# Supply.net
KiCad netlist of a schematic drawn in Altium Designer
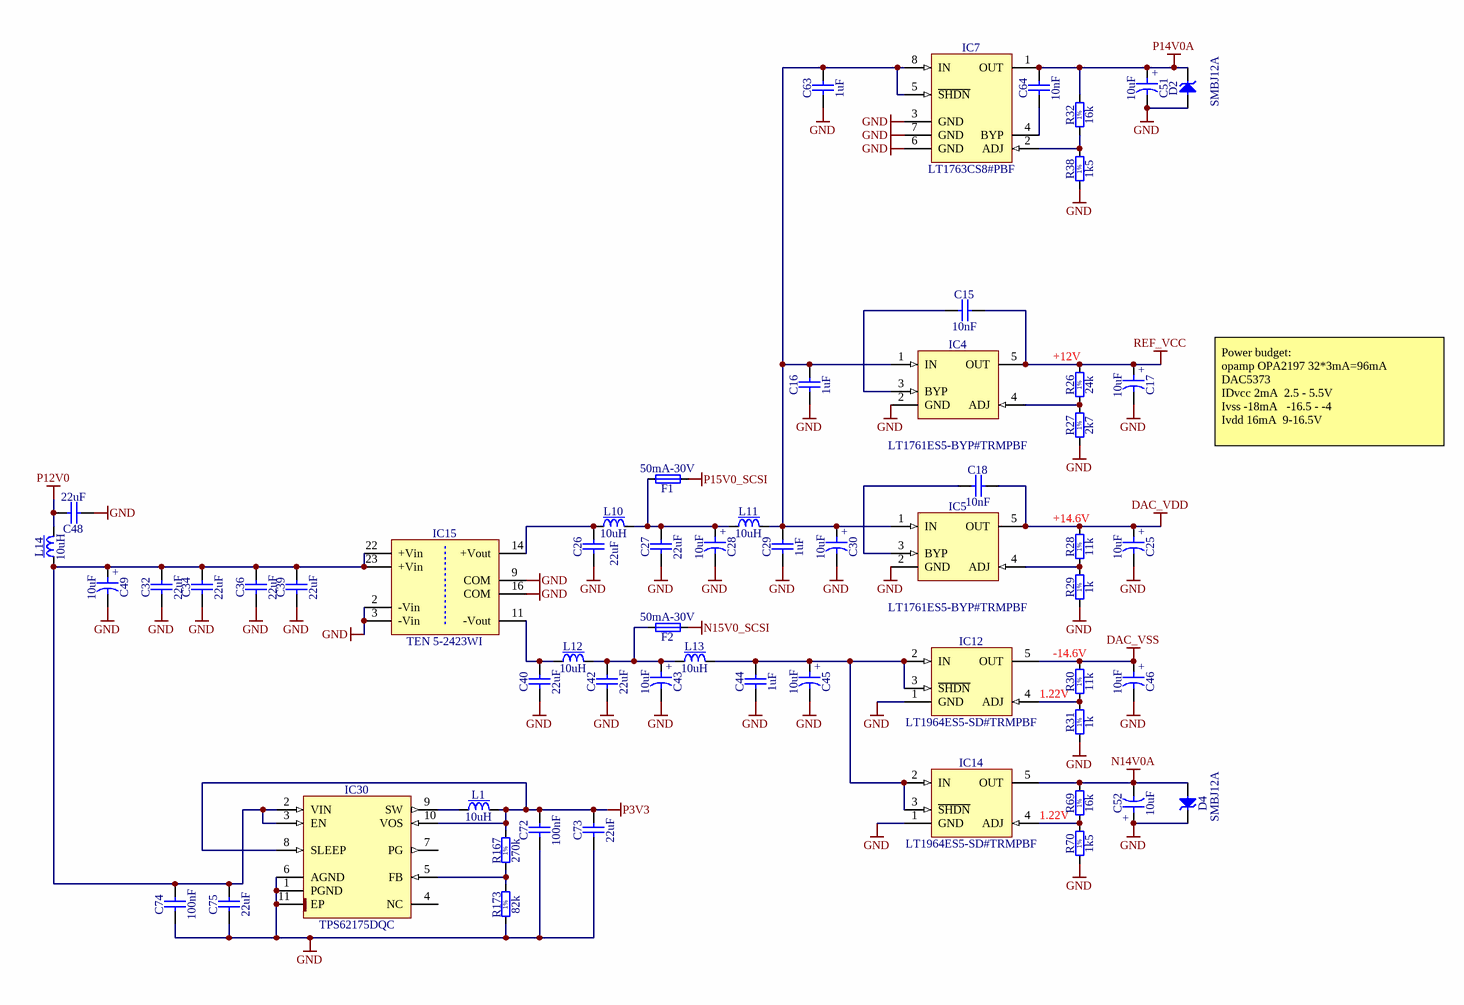
[diagram p0: Supply.SchDoc]

(export (version "E")
  (design (tool "Eeschema 10.0.6"))
  (components
    (comp (ref "C15")
      (value "10nF")
      (footprint "CAPC1608X87N")
      (description "Non-polarised capacitor")
      (fields
        (field (name "PART NUMBER") "CC0603_10NF_50V_10%_X7R")
        (field (name "VOLTAGE") "50V")
        (field (name "AUTHOR") "CERN DEM JLC")
      )
      (libsource (lib "Capacitors") (part "Capacitor - non polarized"))
    )
    (comp (ref "C16")
      (value "1uF")
      (footprint "CAPC1608X87N")
      (description "Non-polarised capacitor")
      (fields
        (field (name "PART NUMBER") "CC0603_1UF_25V_10%_X7R")
        (field (name "VOLTAGE") "25V")
        (field (name "AUTHOR") "CERN DEM JLC")
      )
      (libsource (lib "Capacitors") (part "Capacitor - non polarized"))
    )
    (comp (ref "C17")
      (value "10uF")
      (footprint "CAPMP3216X180N")
      (description "Polarised capacitor")
      (fields
        (field (name "PART NUMBER") "CTE3216-18_10UF_16V_20%_AVX_TCJ")
        (field (name "VOLTAGE") "16V")
        (field (name "AUTHOR") "CERN DEM JLC")
      )
      (libsource (lib "Capacitors") (part "Capacitor - polarized"))
    )
    (comp (ref "C18")
      (value "10nF")
      (footprint "CAPC1608X87N")
      (description "Non-polarised capacitor")
      (fields
        (field (name "PART NUMBER") "CC0603_10NF_50V_10%_X7R")
        (field (name "VOLTAGE") "50V")
        (field (name "AUTHOR") "CERN DEM JLC")
      )
      (libsource (lib "Capacitors") (part "Capacitor - non polarized"))
    )
    (comp (ref "C25")
      (value "10uF")
      (footprint "CAPMP3216X180N")
      (description "Polarised capacitor")
      (fields
        (field (name "PART NUMBER") "CTE3216-18_10UF_16V_20%_AVX_TCJ")
        (field (name "VOLTAGE") "16V")
        (field (name "AUTHOR") "CERN DEM JLC")
      )
      (libsource (lib "Capacitors") (part "Capacitor - polarized"))
    )
    (comp (ref "C26")
      (value "22uF")
      (footprint "CAPC2012X135N")
      (description "Non-polarised capacitor")
      (fields
        (field (name "PART NUMBER") "CC0805_22UF_16V_10%_X5R")
        (field (name "VOLTAGE") "16V")
        (field (name "AUTHOR") "CERN DEM JLC")
      )
      (libsource (lib "Capacitors") (part "Capacitor - non polarized"))
    )
    (comp (ref "C27")
      (value "22uF")
      (footprint "CAPC2012X135N")
      (description "Non-polarised capacitor")
      (fields
        (field (name "PART NUMBER") "CC0805_22UF_16V_10%_X5R")
        (field (name "VOLTAGE") "16V")
        (field (name "AUTHOR") "CERN DEM JLC")
      )
      (libsource (lib "Capacitors") (part "Capacitor - non polarized"))
    )
    (comp (ref "C28")
      (value "10uF")
      (footprint "CAPMP3216X180N")
      (description "Polarised capacitor")
      (fields
        (field (name "PART NUMBER") "CTE3216-18_10UF_16V_20%_AVX_TCJ")
        (field (name "VOLTAGE") "16V")
        (field (name "AUTHOR") "CERN DEM JLC")
      )
      (libsource (lib "Capacitors") (part "Capacitor - polarized"))
    )
    (comp (ref "C29")
      (value "1uF")
      (footprint "CAPC1608X87N")
      (description "Non-polarised capacitor")
      (fields
        (field (name "PART NUMBER") "CC0603_1UF_25V_10%_X7R")
        (field (name "VOLTAGE") "25V")
        (field (name "AUTHOR") "CERN DEM JLC")
      )
      (libsource (lib "Capacitors") (part "Capacitor - non polarized"))
    )
    (comp (ref "C30")
      (value "10uF")
      (footprint "CAPMP3216X180N")
      (description "Polarised capacitor")
      (fields
        (field (name "PART NUMBER") "CTE3216-18_10UF_16V_20%_AVX_TCJ")
        (field (name "VOLTAGE") "16V")
        (field (name "AUTHOR") "CERN DEM JLC")
      )
      (libsource (lib "Capacitors") (part "Capacitor - polarized"))
    )
    (comp (ref "C32")
      (value "22uF")
      (footprint "CAPC2012X135N")
      (description "Non-polarised capacitor")
      (fields
        (field (name "PART NUMBER") "CC0805_22UF_16V_10%_X5R")
        (field (name "VOLTAGE") "16V")
        (field (name "AUTHOR") "CERN DEM JLC")
      )
      (libsource (lib "Capacitors") (part "Capacitor - non polarized"))
    )
    (comp (ref "C34")
      (value "22uF")
      (footprint "CAPC2012X135N")
      (description "Non-polarised capacitor")
      (fields
        (field (name "PART NUMBER") "CC0805_22UF_16V_10%_X5R")
        (field (name "VOLTAGE") "16V")
        (field (name "AUTHOR") "CERN DEM JLC")
      )
      (libsource (lib "Capacitors") (part "Capacitor - non polarized"))
    )
    (comp (ref "C36")
      (value "22uF")
      (footprint "CAPC2012X135N")
      (description "Non-polarised capacitor")
      (fields
        (field (name "PART NUMBER") "CC0805_22UF_16V_10%_X5R")
        (field (name "VOLTAGE") "16V")
        (field (name "AUTHOR") "CERN DEM JLC")
      )
      (libsource (lib "Capacitors") (part "Capacitor - non polarized"))
    )
    (comp (ref "C39")
      (value "22uF")
      (footprint "CAPC2012X135N")
      (description "Non-polarised capacitor")
      (fields
        (field (name "PART NUMBER") "CC0805_22UF_16V_10%_X5R")
        (field (name "VOLTAGE") "16V")
        (field (name "AUTHOR") "CERN DEM JLC")
      )
      (libsource (lib "Capacitors") (part "Capacitor - non polarized"))
    )
    (comp (ref "C40")
      (value "22uF")
      (footprint "CAPC2012X135N")
      (description "Non-polarised capacitor")
      (fields
        (field (name "PART NUMBER") "CC0805_22UF_16V_10%_X5R")
        (field (name "VOLTAGE") "16V")
        (field (name "AUTHOR") "CERN DEM JLC")
      )
      (libsource (lib "Capacitors") (part "Capacitor - non polarized"))
    )
    (comp (ref "C42")
      (value "22uF")
      (footprint "CAPC2012X135N")
      (description "Non-polarised capacitor")
      (fields
        (field (name "PART NUMBER") "CC0805_22UF_16V_10%_X5R")
        (field (name "VOLTAGE") "16V")
        (field (name "AUTHOR") "CERN DEM JLC")
      )
      (libsource (lib "Capacitors") (part "Capacitor - non polarized"))
    )
    (comp (ref "C43")
      (value "10uF")
      (footprint "CAPMP3216X180N")
      (description "Polarised capacitor")
      (fields
        (field (name "PART NUMBER") "CTE3216-18_10UF_16V_20%_AVX_TCJ")
        (field (name "VOLTAGE") "16V")
        (field (name "AUTHOR") "CERN DEM JLC")
      )
      (libsource (lib "Capacitors") (part "Capacitor - polarized"))
    )
    (comp (ref "C44")
      (value "1uF")
      (footprint "CAPC1608X87N")
      (description "Non-polarised capacitor")
      (fields
        (field (name "PART NUMBER") "CC0603_1UF_25V_10%_X7R")
        (field (name "VOLTAGE") "25V")
        (field (name "AUTHOR") "CERN DEM JLC")
      )
      (libsource (lib "Capacitors") (part "Capacitor - non polarized"))
    )
    (comp (ref "C45")
      (value "10uF")
      (footprint "CAPMP3216X180N")
      (description "Polarised capacitor")
      (fields
        (field (name "PART NUMBER") "CTE3216-18_10UF_16V_20%_AVX_TCJ")
        (field (name "VOLTAGE") "16V")
        (field (name "AUTHOR") "CERN DEM JLC")
      )
      (libsource (lib "Capacitors") (part "Capacitor - polarized"))
    )
    (comp (ref "C46")
      (value "10uF")
      (footprint "CAPMP3216X180N")
      (description "Polarised capacitor")
      (fields
        (field (name "PART NUMBER") "CTE3216-18_10UF_16V_20%_AVX_TCJ")
        (field (name "VOLTAGE") "16V")
        (field (name "AUTHOR") "CERN DEM JLC")
      )
      (libsource (lib "Capacitors") (part "Capacitor - polarized"))
    )
    (comp (ref "C48")
      (value "22uF")
      (footprint "CAPC2012X135N")
      (description "Non-polarised capacitor")
      (fields
        (field (name "PART NUMBER") "CC0805_22UF_16V_10%_X5R")
        (field (name "VOLTAGE") "16V")
        (field (name "AUTHOR") "CERN DEM JLC")
      )
      (libsource (lib "Capacitors") (part "Capacitor - non polarized"))
    )
    (comp (ref "C49")
      (value "10uF")
      (footprint "CAPMP3216X180N")
      (description "Polarised capacitor")
      (fields
        (field (name "PART NUMBER") "CTE3216-18_10UF_16V_20%_AVX_TCJ")
        (field (name "VOLTAGE") "16V")
        (field (name "AUTHOR") "CERN DEM JLC")
      )
      (libsource (lib "Capacitors") (part "Capacitor - polarized"))
    )
    (comp (ref "C51")
      (value "10uF")
      (footprint "CAPMP3216X180N")
      (description "Polarised capacitor")
      (fields
        (field (name "PART NUMBER") "CTE3216-18_10UF_16V_20%_AVX_TCJ")
        (field (name "VOLTAGE") "16V")
        (field (name "AUTHOR") "CERN DEM JLC")
      )
      (libsource (lib "Capacitors") (part "Capacitor - polarized"))
    )
    (comp (ref "C52")
      (value "10uF")
      (footprint "CAPMP3216X180N")
      (description "Polarised capacitor")
      (fields
        (field (name "PART NUMBER") "CTE3216-18_10UF_16V_20%_AVX_TCJ")
        (field (name "VOLTAGE") "16V")
        (field (name "AUTHOR") "CERN DEM JLC")
      )
      (libsource (lib "Capacitors") (part "Capacitor - polarized"))
    )
    (comp (ref "C63")
      (value "1uF")
      (footprint "CAPC1608X87N")
      (description "Non-polarised capacitor")
      (fields
        (field (name "PART NUMBER") "CC0603_1UF_25V_10%_X7R")
        (field (name "VOLTAGE") "25V")
        (field (name "AUTHOR") "CERN DEM JLC")
      )
      (libsource (lib "Capacitors") (part "Capacitor - non polarized"))
    )
    (comp (ref "C64")
      (value "10nF")
      (footprint "CAPC1608X87N")
      (description "Non-polarised capacitor")
      (fields
        (field (name "PART NUMBER") "CC0603_10NF_50V_10%_X7R")
        (field (name "VOLTAGE") "50V")
        (field (name "AUTHOR") "CERN DEM JLC")
      )
      (libsource (lib "Capacitors") (part "Capacitor - non polarized"))
    )
    (comp (ref "C72")
      (value "100nF")
      (footprint "CAPC1005X55N")
      (description "Non-polarised capacitor")
      (fields
        (field (name "PART NUMBER") "CC0402_100NF_16V_10%_X5R")
        (field (name "VOLTAGE") "16V")
        (field (name "AUTHOR") "CERN DEM JLC")
      )
      (libsource (lib "Capacitors") (part "Capacitor - non polarized"))
    )
    (comp (ref "C73")
      (value "22uF")
      (footprint "CAPC2012X135N")
      (description "Non-polarised capacitor")
      (fields
        (field (name "PART NUMBER") "CC0805_22UF_16V_10%_X5R")
        (field (name "VOLTAGE") "16V")
        (field (name "AUTHOR") "CERN DEM JLC")
      )
      (libsource (lib "Capacitors") (part "Capacitor - non polarized"))
    )
    (comp (ref "C74")
      (value "100nF")
      (footprint "CAPC1005X55N")
      (description "Non-polarised capacitor")
      (fields
        (field (name "PART NUMBER") "CC0402_100NF_16V_10%_X5R")
        (field (name "VOLTAGE") "16V")
        (field (name "AUTHOR") "CERN DEM JLC")
      )
      (libsource (lib "Capacitors") (part "Capacitor - non polarized"))
    )
    (comp (ref "C75")
      (value "22uF")
      (footprint "CAPC2012X135N")
      (description "Non-polarised capacitor")
      (fields
        (field (name "PART NUMBER") "CC0805_22UF_16V_10%_X5R")
        (field (name "VOLTAGE") "16V")
        (field (name "AUTHOR") "CERN DEM JLC")
      )
      (libsource (lib "Capacitors") (part "Capacitor - non polarized"))
    )
    (comp (ref "D2")
      (value "SMBJ12A")
      (footprint "DIOM5336X265N")
      (description "Zener Diode")
      (fields
        (field (name "VOLTAGE") "12V")
        (field (name "POWER") "600W")
        (field (name "AUTHOR") "CERN DEM JLC")
      )
      (libsource (lib "ICs And Semiconductors") (part "Diode Zener"))
    )
    (comp (ref "D4")
      (value "SMBJ12A")
      (footprint "DIOM5336X265N")
      (description "Zener Diode")
      (fields
        (field (name "VOLTAGE") "12V")
        (field (name "POWER") "600W")
        (field (name "AUTHOR") "CERN DEM JLC")
      )
      (libsource (lib "ICs And Semiconductors") (part "Diode Zener"))
    )
    (comp (ref "F1")
      (value "50mA-30V")
      (footprint "FUSRC3226X85N")
      (description "Fuse")
      (fields
        (field (name "PART NUMBER") "FUSR1210_TYCO-MICROSMD005F")
        (field (name "MANUFACTURER") "TYCO ELECTRONICS")
        (field (name "AUTHOR") "CERN DEM JLC")
      )
      (libsource (lib "Eletro-mechanical") (part "Fuse"))
    )
    (comp (ref "F2")
      (value "50mA-30V")
      (footprint "FUSRC3226X85N")
      (description "Fuse")
      (fields
        (field (name "PART NUMBER") "FUSR1210_TYCO-MICROSMD005F")
        (field (name "MANUFACTURER") "TYCO ELECTRONICS")
        (field (name "AUTHOR") "CERN DEM JLC")
      )
      (libsource (lib "Eletro-mechanical") (part "Fuse"))
    )
    (comp (ref "IC4")
      (value "LT1761ES5-BYP#TRMPBF")
      (footprint "SOT95P280X100-5N")
      (description "100mA, Low Noise, LDO Micropower Adjustable Regulator in SOT-23")
      (fields (field (name "MANUFACTURER") "LINEAR TECHNOLOGY") (field (name "AUTHOR") "CERN DEM MR"))
      (libsource (lib "ICs And Semiconductors") (part "LT1761-BYP"))
    )
    (comp (ref "IC5")
      (value "LT1761ES5-BYP#TRMPBF")
      (footprint "SOT95P280X100-5N")
      (description "100mA, Low Noise, LDO Micropower Adjustable Regulator in SOT-23")
      (fields (field (name "MANUFACTURER") "LINEAR TECHNOLOGY") (field (name "AUTHOR") "CERN DEM MR"))
      (libsource (lib "ICs And Semiconductors") (part "LT1761-BYP"))
    )
    (comp (ref "IC7")
      (value "LT1763CS8#PBF")
      (footprint "SOIC127P600X175-8N")
      (description "1.22V to 20V 500mA, Low Noise, LDO Adjustable Micropower Regulator")
      (fields (field (name "MANUFACTURER") "LINEAR TECHNOLOGY") (field (name "AUTHOR") "CERN DEM JLC"))
      (libsource (lib "ICs And Semiconductors") (part "LT1763xS8"))
    )
    (comp (ref "IC12")
      (value "LT1964ES5-SD#TRMPBF")
      (footprint "SOT95P280X100-5N")
      (description "200mA, Low Noise, Low Dropout Negative Micropower Regulator")
      (fields (field (name "MANUFACTURER") "LINEAR TECHNOLOGY") (field (name "AUTHOR") "CERN DEM JLC"))
      (libsource (lib "ICs And Semiconductors") (part "LT1964-SD"))
    )
    (comp (ref "IC14")
      (value "LT1964ES5-SD#TRMPBF")
      (footprint "SOT95P280X100-5N")
      (description "200mA, Low Noise, Low Dropout Negative Micropower Regulator")
      (fields (field (name "MANUFACTURER") "LINEAR TECHNOLOGY") (field (name "AUTHOR") "CERN DEM JLC"))
      (libsource (lib "ICs And Semiconductors") (part "LT1964-SD"))
    )
    (comp (ref "IC15")
      (value "TEN 5-2423WI")
      (footprint "DCDC_TRACO_TEN5WI")
      (description "TRACO, TEN5 Serie, Dual Outputs DCDC Converter")
      (fields (field (name "MANUFACTURER") "TRACO POWER") (field (name "AUTHOR") "CERN DEM JMW"))
      (libsource (lib "ICs And Semiconductors") (part "DCDC_TRACO_TEN5_Dual Outputs"))
    )
    (comp (ref "IC30")
      (value "TPS62175DQC")
      (footprint "SON50P200X300X80-11N-R94X250")
      (description "4.75-28VDC to 1-6VDC, 500mA Step-Down Converter With Sleep Mode")
      (fields (field (name "MANUFACTURER") "TEXAS INSTRUMENTS") (field (name "AUTHOR") "CERN DEM JMW"))
      (libsource (lib "ICs And Semiconductors") (part "TPS62175"))
    )
    (comp (ref "L1")
      (value "10uH")
      (footprint "IND_MURATA-PS_8400")
      (description "Inductor With Core")
      (fields
        (field (name "PART NUMBER") "IND_10UH_10%_MURATA-PS_8400")
        (field (name "POWER") "950mA")
        (field (name "AUTHOR") "CERN DEM JLC")
      )
      (libsource (lib "") (part "Inductor With Magnetic core_1"))
    )
    (comp (ref "L10")
      (value "10uH")
      (footprint "IND_MURATA-PS_8400")
      (description "Inductor With Core")
      (fields
        (field (name "PART NUMBER") "IND_10UH_10%_MURATA-PS_8400")
        (field (name "POWER") "950mA")
        (field (name "AUTHOR") "CERN DEM JLC")
      )
      (libsource (lib "") (part "Inductor With Magnetic core_1"))
    )
    (comp (ref "L11")
      (value "10uH")
      (footprint "IND_MURATA-PS_8400")
      (description "Inductor With Core")
      (fields
        (field (name "PART NUMBER") "IND_10UH_10%_MURATA-PS_8400")
        (field (name "POWER") "950mA")
        (field (name "AUTHOR") "CERN DEM JLC")
      )
      (libsource (lib "") (part "Inductor With Magnetic core_1"))
    )
    (comp (ref "L12")
      (value "10uH")
      (footprint "IND_MURATA-PS_8400")
      (description "Inductor With Core")
      (fields
        (field (name "PART NUMBER") "IND_10UH_10%_MURATA-PS_8400")
        (field (name "POWER") "950mA")
        (field (name "AUTHOR") "CERN DEM JLC")
      )
      (libsource (lib "") (part "Inductor With Magnetic core_1"))
    )
    (comp (ref "L13")
      (value "10uH")
      (footprint "IND_MURATA-PS_8400")
      (description "Inductor With Core")
      (fields
        (field (name "PART NUMBER") "IND_10UH_10%_MURATA-PS_8400")
        (field (name "POWER") "950mA")
        (field (name "AUTHOR") "CERN DEM JLC")
      )
      (libsource (lib "") (part "Inductor With Magnetic core_1"))
    )
    (comp (ref "L14")
      (value "10uH")
      (footprint "IND_MURATA-PS_8400")
      (description "Inductor With Core")
      (fields
        (field (name "PART NUMBER") "IND_10UH_10%_MURATA-PS_8400")
        (field (name "POWER") "950mA")
        (field (name "AUTHOR") "CERN DEM JLC")
      )
      (libsource (lib "Inductors & Transformers") (part "Inductor With Magnetic core"))
    )
    (comp (ref "R26")
      (value "24k")
      (footprint "RESC1608X55N")
      (description "Resistor - 1%")
      (fields
        (field (name "PART NUMBER") "R0603_24K_1%_0.1W_100PPM")
        (field (name "POWER") "0.1W")
        (field (name "AUTHOR") "CERN DEM JLC")
      )
      (libsource (lib "Resistors") (part "Resistor - 1%"))
    )
    (comp (ref "R27")
      (value "2k7")
      (footprint "RESC1608X55N")
      (description "Resistor - 1%")
      (fields
        (field (name "PART NUMBER") "R0603_2K7_1%_0.1W_100PPM")
        (field (name "POWER") "0.1W")
        (field (name "AUTHOR") "CERN DEM JLC")
      )
      (libsource (lib "Resistors") (part "Resistor - 1%"))
    )
    (comp (ref "R28")
      (value "11k")
      (footprint "RESC1608X55N")
      (description "Resistor - 1%")
      (fields
        (field (name "PART NUMBER") "R0603_11K_1%_0.1W_100PPM")
        (field (name "POWER") "0.1W")
        (field (name "AUTHOR") "CERN DEM JLC")
      )
      (libsource (lib "Resistors") (part "Resistor - 1%"))
    )
    (comp (ref "R29")
      (value "1k")
      (footprint "RESC1608X55N")
      (description "Resistor - 1%")
      (fields
        (field (name "PART NUMBER") "R0603_1K_1%_0.1W_100PPM")
        (field (name "POWER") "0.1W")
        (field (name "AUTHOR") "CERN DEM JLC")
      )
      (libsource (lib "Resistors") (part "Resistor - 1%"))
    )
    (comp (ref "R30")
      (value "11k")
      (footprint "RESC1608X55N")
      (description "Resistor - 1%")
      (fields
        (field (name "PART NUMBER") "R0603_11K_1%_0.1W_100PPM")
        (field (name "POWER") "0.1W")
        (field (name "AUTHOR") "CERN DEM JLC")
      )
      (libsource (lib "Resistors") (part "Resistor - 1%"))
    )
    (comp (ref "R31")
      (value "1k")
      (footprint "RESC1608X55N")
      (description "Resistor - 1%")
      (fields
        (field (name "PART NUMBER") "R0603_1K_1%_0.1W_100PPM")
        (field (name "POWER") "0.1W")
        (field (name "AUTHOR") "CERN DEM JLC")
      )
      (libsource (lib "Resistors") (part "Resistor - 1%"))
    )
    (comp (ref "R32")
      (value "16k")
      (footprint "RESC1608X55N")
      (description "Resistor - 1%")
      (fields
        (field (name "PART NUMBER") "R0603_16K_1%_0.1W_100PPM")
        (field (name "POWER") "0.1W")
        (field (name "AUTHOR") "CERN DEM JLC")
      )
      (libsource (lib "Resistors") (part "Resistor - 1%"))
    )
    (comp (ref "R38")
      (value "1k5")
      (footprint "RESC1608X55N")
      (description "Resistor - 1%")
      (fields
        (field (name "PART NUMBER") "R0603_1K5_1%_0.1W_100PPM")
        (field (name "POWER") "0.1W")
        (field (name "AUTHOR") "CERN DEM JLC")
      )
      (libsource (lib "Resistors") (part "Resistor - 1%"))
    )
    (comp (ref "R69")
      (value "16k")
      (footprint "RESC1608X55N")
      (description "Resistor - 1%")
      (fields
        (field (name "PART NUMBER") "R0603_16K_1%_0.1W_100PPM")
        (field (name "POWER") "0.1W")
        (field (name "AUTHOR") "CERN DEM JLC")
      )
      (libsource (lib "Resistors") (part "Resistor - 1%"))
    )
    (comp (ref "R70")
      (value "1k5")
      (footprint "RESC1608X55N")
      (description "Resistor - 1%")
      (fields
        (field (name "PART NUMBER") "R0603_1K5_1%_0.1W_100PPM")
        (field (name "POWER") "0.1W")
        (field (name "AUTHOR") "CERN DEM JLC")
      )
      (libsource (lib "Resistors") (part "Resistor - 1%"))
    )
    (comp (ref "R167")
      (value "270k")
      (footprint "RESC1608X55N")
      (description "Resistor - 1%")
      (fields
        (field (name "PART NUMBER") "R0603_270K_1%_0.1W_100PPM")
        (field (name "POWER") "0.1W")
        (field (name "AUTHOR") "CERN DEM JLC")
      )
      (libsource (lib "Resistors") (part "Resistor - 1%"))
    )
    (comp (ref "R173")
      (value "82k")
      (footprint "RESC1608X55N")
      (description "Resistor - 1%")
      (fields
        (field (name "PART NUMBER") "R0603_82K_1%_0.1W_100PPM")
        (field (name "POWER") "0.1W")
        (field (name "AUTHOR") "CERN DEM JLC")
      )
      (libsource (lib "Resistors") (part "Resistor - 1%"))
    )
  )
  (nets
    (net (code "1") (name "DAC_VDD") (class "Default")
      (node (ref "C18") (pin "2") (pinfunction "2_2") (pintype "passive"))
      (node (ref "C25") (pin "1") (pinfunction "1_1") (pintype "passive"))
      (node (ref "IC5") (pin "5") (pinfunction "OUT_5") (pintype "power_in"))
      (node (ref "R28") (pin "2") (pinfunction "2_2") (pintype "passive"))
    )
    (net (code "2") (name "DAC_VSS") (class "Default")
      (node (ref "C46") (pin "1") (pinfunction "1_1") (pintype "passive"))
      (node (ref "IC12") (pin "5") (pinfunction "OUT_5") (pintype "power_in"))
      (node (ref "R30") (pin "2") (pinfunction "2_2") (pintype "passive"))
    )
    (net (code "3") (name "GND") (class "Default")
      (node (ref "C16") (pin "1") (pinfunction "1_1") (pintype "passive"))
      (node (ref "C17") (pin "2") (pinfunction "2_2") (pintype "passive"))
      (node (ref "C25") (pin "2") (pinfunction "2_2") (pintype "passive"))
      (node (ref "C26") (pin "1") (pinfunction "1_1") (pintype "passive"))
      (node (ref "C27") (pin "1") (pinfunction "1_1") (pintype "passive"))
      (node (ref "C28") (pin "2") (pinfunction "2_2") (pintype "passive"))
      (node (ref "C29") (pin "1") (pinfunction "1_1") (pintype "passive"))
      (node (ref "C30") (pin "2") (pinfunction "2_2") (pintype "passive"))
      (node (ref "C32") (pin "1") (pinfunction "1_1") (pintype "passive"))
      (node (ref "C34") (pin "1") (pinfunction "1_1") (pintype "passive"))
      (node (ref "C36") (pin "1") (pinfunction "1_1") (pintype "passive"))
      (node (ref "C39") (pin "1") (pinfunction "1_1") (pintype "passive"))
      (node (ref "C40") (pin "1") (pinfunction "1_1") (pintype "passive"))
      (node (ref "C42") (pin "1") (pinfunction "1_1") (pintype "passive"))
      (node (ref "C43") (pin "2") (pinfunction "2_2") (pintype "passive"))
      (node (ref "C44") (pin "1") (pinfunction "1_1") (pintype "passive"))
      (node (ref "C45") (pin "2") (pinfunction "2_2") (pintype "passive"))
      (node (ref "C46") (pin "2") (pinfunction "2_2") (pintype "passive"))
      (node (ref "C48") (pin "1") (pinfunction "1_1") (pintype "passive"))
      (node (ref "C49") (pin "2") (pinfunction "2_2") (pintype "passive"))
      (node (ref "C51") (pin "2") (pinfunction "2_2") (pintype "passive"))
      (node (ref "C52") (pin "1") (pinfunction "1_1") (pintype "passive"))
      (node (ref "C63") (pin "1") (pinfunction "1_1") (pintype "passive"))
      (node (ref "C72") (pin "1") (pinfunction "1_1") (pintype "passive"))
      (node (ref "C73") (pin "1") (pinfunction "1_1") (pintype "passive"))
      (node (ref "C74") (pin "1") (pinfunction "1_1") (pintype "passive"))
      (node (ref "C75") (pin "1") (pinfunction "1_1") (pintype "passive"))
      (node (ref "D2") (pin "2") (pinfunction "A_2") (pintype "passive"))
      (node (ref "D4") (pin "1") (pinfunction "C_1") (pintype "passive"))
      (node (ref "IC12") (pin "1") (pinfunction "GND_1") (pintype "power_in"))
      (node (ref "IC14") (pin "1") (pinfunction "GND_1") (pintype "power_in"))
      (node (ref "IC15") (pin "16") (pinfunction "COM_16") (pintype "power_in"))
      (node (ref "IC15") (pin "2") (pinfunction "-Vin_2") (pintype "power_in"))
      (node (ref "IC15") (pin "3") (pinfunction "-Vin_3") (pintype "power_in"))
      (node (ref "IC15") (pin "9") (pinfunction "COM_9") (pintype "power_in"))
      (node (ref "IC30") (pin "1") (pinfunction "PGND_1") (pintype "power_in"))
      (node (ref "IC30") (pin "11") (pinfunction "EP_11") (pintype "power_in"))
      (node (ref "IC30") (pin "6") (pinfunction "AGND_6") (pintype "power_in"))
      (node (ref "IC4") (pin "2") (pinfunction "GND_2") (pintype "power_in"))
      (node (ref "IC5") (pin "2") (pinfunction "GND_2") (pintype "power_in"))
      (node (ref "IC7") (pin "3") (pinfunction "GND_3") (pintype "power_in"))
      (node (ref "IC7") (pin "6") (pinfunction "GND_6") (pintype "power_in"))
      (node (ref "IC7") (pin "7") (pinfunction "GND_7") (pintype "power_in"))
      (node (ref "R173") (pin "1") (pinfunction "1_1") (pintype "passive"))
      (node (ref "R27") (pin "1") (pinfunction "1_1") (pintype "passive"))
      (node (ref "R29") (pin "1") (pinfunction "1_1") (pintype "passive"))
      (node (ref "R31") (pin "1") (pinfunction "1_1") (pintype "passive"))
      (node (ref "R38") (pin "1") (pinfunction "1_1") (pintype "passive"))
      (node (ref "R70") (pin "1") (pinfunction "1_1") (pintype "passive"))
    )
    (net (code "4") (name "N14V0A") (class "Default")
      (node (ref "C52") (pin "2") (pinfunction "2_2") (pintype "passive"))
      (node (ref "D4") (pin "2") (pinfunction "A_2") (pintype "passive"))
      (node (ref "IC14") (pin "5") (pinfunction "OUT_5") (pintype "power_in"))
      (node (ref "R69") (pin "2") (pinfunction "2_2") (pintype "passive"))
    )
    (net (code "5") (name "N15V0_SCSI") (class "Default")
      (node (ref "F2") (pin "1") (pinfunction "1_1") (pintype "passive"))
    )
    (net (code "6") (name "Net-(C27-Pad2)") (class "Default")
      (node (ref "C27") (pin "2") (pinfunction "2_2") (pintype "passive"))
      (node (ref "C28") (pin "1") (pinfunction "1_1") (pintype "passive"))
      (node (ref "F1") (pin "2") (pinfunction "2_2") (pintype "passive"))
      (node (ref "L10") (pin "2") (pinfunction "2_2") (pintype "passive"))
      (node (ref "L11") (pin "1") (pinfunction "1_1") (pintype "passive"))
    )
    (net (code "7") (name "Net-(C42-Pad2)") (class "Default")
      (node (ref "C42") (pin "2") (pinfunction "2_2") (pintype "passive"))
      (node (ref "C43") (pin "1") (pinfunction "1_1") (pintype "passive"))
      (node (ref "F2") (pin "2") (pinfunction "2_2") (pintype "passive"))
      (node (ref "L12") (pin "2") (pinfunction "2_2") (pintype "passive"))
      (node (ref "L13") (pin "1") (pinfunction "1_1") (pintype "passive"))
    )
    (net (code "8") (name "Net-(IC4-ADJ)") (class "Default")
      (node (ref "IC4") (pin "4") (pinfunction "ADJ_4") (pintype "input"))
      (node (ref "R26") (pin "1") (pinfunction "1_1") (pintype "passive"))
      (node (ref "R27") (pin "2") (pinfunction "2_2") (pintype "passive"))
    )
    (net (code "9") (name "Net-(IC4-BYP)") (class "Default")
      (node (ref "C15") (pin "1") (pinfunction "1_1") (pintype "passive"))
      (node (ref "IC4") (pin "3") (pinfunction "BYP_3") (pintype "input"))
    )
    (net (code "10") (name "Net-(IC4-IN)") (class "Default")
      (node (ref "C16") (pin "2") (pinfunction "2_2") (pintype "passive"))
      (node (ref "C29") (pin "2") (pinfunction "2_2") (pintype "passive"))
      (node (ref "C30") (pin "1") (pinfunction "1_1") (pintype "passive"))
      (node (ref "C63") (pin "2") (pinfunction "2_2") (pintype "passive"))
      (node (ref "IC4") (pin "1") (pinfunction "IN_1") (pintype "input"))
      (node (ref "IC5") (pin "1") (pinfunction "IN_1") (pintype "input"))
      (node (ref "IC7") (pin "5") (pinfunction "~{SHDN}_5") (pintype "input"))
      (node (ref "IC7") (pin "8") (pinfunction "IN_8") (pintype "input"))
      (node (ref "L11") (pin "2") (pinfunction "2_2") (pintype "passive"))
    )
    (net (code "11") (name "Net-(IC5-ADJ)") (class "Default")
      (node (ref "IC5") (pin "4") (pinfunction "ADJ_4") (pintype "input"))
      (node (ref "R28") (pin "1") (pinfunction "1_1") (pintype "passive"))
      (node (ref "R29") (pin "2") (pinfunction "2_2") (pintype "passive"))
    )
    (net (code "12") (name "Net-(IC5-BYP)") (class "Default")
      (node (ref "C18") (pin "1") (pinfunction "1_1") (pintype "passive"))
      (node (ref "IC5") (pin "3") (pinfunction "BYP_3") (pintype "input"))
    )
    (net (code "13") (name "Net-(IC7-ADJ)") (class "Default")
      (node (ref "IC7") (pin "2") (pinfunction "ADJ_2") (pintype "input"))
      (node (ref "R32") (pin "1") (pinfunction "1_1") (pintype "passive"))
      (node (ref "R38") (pin "2") (pinfunction "2_2") (pintype "passive"))
    )
    (net (code "14") (name "Net-(IC7-BYP)") (class "Default")
      (node (ref "C64") (pin "1") (pinfunction "1_1") (pintype "passive"))
      (node (ref "IC7") (pin "4") (pinfunction "BYP_4") (pintype "passive"))
    )
    (net (code "15") (name "Net-(IC12-ADJ)") (class "Default")
      (node (ref "IC12") (pin "4") (pinfunction "ADJ_4") (pintype "input"))
      (node (ref "R30") (pin "1") (pinfunction "1_1") (pintype "passive"))
      (node (ref "R31") (pin "2") (pinfunction "2_2") (pintype "passive"))
    )
    (net (code "16") (name "Net-(IC12-IN)") (class "Default")
      (node (ref "C44") (pin "2") (pinfunction "2_2") (pintype "passive"))
      (node (ref "C45") (pin "1") (pinfunction "1_1") (pintype "passive"))
      (node (ref "IC12") (pin "2") (pinfunction "IN_2") (pintype "input"))
      (node (ref "IC12") (pin "3") (pinfunction "~{SHDN}_3") (pintype "input"))
      (node (ref "IC14") (pin "2") (pinfunction "IN_2") (pintype "input"))
      (node (ref "IC14") (pin "3") (pinfunction "~{SHDN}_3") (pintype "input"))
      (node (ref "L13") (pin "2") (pinfunction "2_2") (pintype "passive"))
    )
    (net (code "17") (name "Net-(IC14-ADJ)") (class "Default")
      (node (ref "IC14") (pin "4") (pinfunction "ADJ_4") (pintype "input"))
      (node (ref "R69") (pin "1") (pinfunction "1_1") (pintype "passive"))
      (node (ref "R70") (pin "2") (pinfunction "2_2") (pintype "passive"))
    )
    (net (code "18") (name "Net-(IC15-+Vout)") (class "Default")
      (node (ref "C26") (pin "2") (pinfunction "2_2") (pintype "passive"))
      (node (ref "IC15") (pin "14") (pinfunction "+Vout_14") (pintype "power_in"))
      (node (ref "L10") (pin "1") (pinfunction "1_1") (pintype "passive"))
    )
    (net (code "19") (name "Net-(IC15--Vout)") (class "Default")
      (node (ref "C40") (pin "2") (pinfunction "2_2") (pintype "passive"))
      (node (ref "IC15") (pin "11") (pinfunction "-Vout_11") (pintype "power_in"))
      (node (ref "L12") (pin "1") (pinfunction "1_1") (pintype "passive"))
    )
    (net (code "20") (name "Net-(IC30-EN)") (class "Default")
      (node (ref "C32") (pin "2") (pinfunction "2_2") (pintype "passive"))
      (node (ref "C34") (pin "2") (pinfunction "2_2") (pintype "passive"))
      (node (ref "C36") (pin "2") (pinfunction "2_2") (pintype "passive"))
      (node (ref "C39") (pin "2") (pinfunction "2_2") (pintype "passive"))
      (node (ref "C49") (pin "1") (pinfunction "1_1") (pintype "passive"))
      (node (ref "C74") (pin "2") (pinfunction "2_2") (pintype "passive"))
      (node (ref "C75") (pin "2") (pinfunction "2_2") (pintype "passive"))
      (node (ref "IC15") (pin "22") (pinfunction "+Vin_22") (pintype "power_in"))
      (node (ref "IC15") (pin "23") (pinfunction "+Vin_23") (pintype "power_in"))
      (node (ref "IC30") (pin "2") (pinfunction "VIN_2") (pintype "input"))
      (node (ref "IC30") (pin "3") (pinfunction "EN_3") (pintype "input"))
      (node (ref "L14") (pin "1") (pinfunction "1_1") (pintype "passive"))
    )
    (net (code "21") (name "Net-(IC30-FB)") (class "Default")
      (node (ref "IC30") (pin "5") (pinfunction "FB_5") (pintype "input"))
      (node (ref "R167") (pin "1") (pinfunction "1_1") (pintype "passive"))
      (node (ref "R173") (pin "2") (pinfunction "2_2") (pintype "passive"))
    )
    (net (code "22") (name "Net-(IC30-SW)") (class "Default")
      (node (ref "IC30") (pin "9") (pinfunction "SW_9") (pintype "output"))
      (node (ref "L1") (pin "1") (pinfunction "1_1") (pintype "passive"))
    )
    (net (code "23") (name "P3V3") (class "Default")
      (node (ref "C72") (pin "2") (pinfunction "2_2") (pintype "passive"))
      (node (ref "C73") (pin "2") (pinfunction "2_2") (pintype "passive"))
      (node (ref "IC30") (pin "10") (pinfunction "VOS_10") (pintype "input"))
      (node (ref "IC30") (pin "8") (pinfunction "SLEEP_8") (pintype "input"))
      (node (ref "L1") (pin "2") (pinfunction "2_2") (pintype "passive"))
      (node (ref "R167") (pin "2") (pinfunction "2_2") (pintype "passive"))
    )
    (net (code "24") (name "P12V0") (class "Default")
      (node (ref "C48") (pin "2") (pinfunction "2_2") (pintype "passive"))
      (node (ref "L14") (pin "2") (pinfunction "2_2") (pintype "passive"))
    )
    (net (code "25") (name "P14V0A") (class "Default")
      (node (ref "C51") (pin "1") (pinfunction "1_1") (pintype "passive"))
      (node (ref "C64") (pin "2") (pinfunction "2_2") (pintype "passive"))
      (node (ref "D2") (pin "1") (pinfunction "C_1") (pintype "passive"))
      (node (ref "IC7") (pin "1") (pinfunction "OUT_1") (pintype "power_in"))
      (node (ref "R32") (pin "2") (pinfunction "2_2") (pintype "passive"))
    )
    (net (code "26") (name "P15V0_SCSI") (class "Default")
      (node (ref "F1") (pin "1") (pinfunction "1_1") (pintype "passive"))
    )
    (net (code "27") (name "REF_VCC") (class "Default")
      (node (ref "C15") (pin "2") (pinfunction "2_2") (pintype "passive"))
      (node (ref "C17") (pin "1") (pinfunction "1_1") (pintype "passive"))
      (node (ref "IC4") (pin "5") (pinfunction "OUT_5") (pintype "power_in"))
      (node (ref "R26") (pin "2") (pinfunction "2_2") (pintype "passive"))
    )
    (net (code "28") (name "unconnected-(IC30-NC-Pad4)") (class "Default")
      (node (ref "IC30") (pin "4") (pinfunction "NC_4") (pintype "passive"))
    )
    (net (code "29") (name "unconnected-(IC30-PG-Pad7)") (class "Default")
      (node (ref "IC30") (pin "7") (pinfunction "PG_7") (pintype "output"))
    )
  )
)
